# fab-psoc.net
KiCad netlist of a schematic drawn in EAGLE
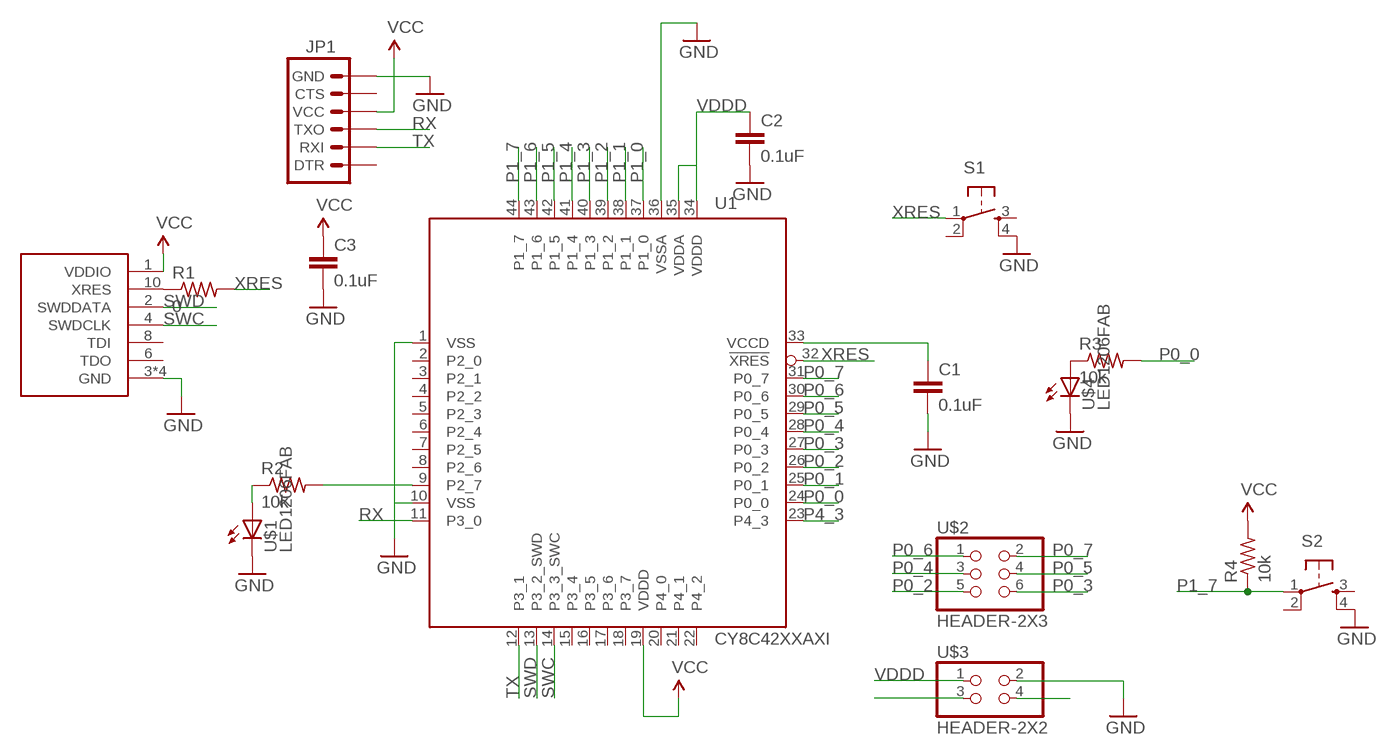
[diagram p0: schematic, sheet 1]

(export (version "E")
  (design (tool "Eeschema 10.0.6"))
  (components
    (comp (ref "C1")
      (value "0.1uF")
      (footprint "eagle-import:C1206FAB")
      (libsource (lib "eagle-import") (part "CAPACITOR1206FAB"))
    )
    (comp (ref "C2")
      (value "0.1uF")
      (footprint "eagle-import:C1206FAB")
      (libsource (lib "eagle-import") (part "CAPACITOR1206FAB"))
    )
    (comp (ref "C3")
      (value "0.1uF")
      (footprint "eagle-import:C1206FAB")
      (libsource (lib "eagle-import") (part "CAPACITOR1206FAB"))
    )
    (comp (ref "JP1")
      (value "FTDI-SMD")
      (footprint "eagle-import:FTDI-SMD")
      (libsource (lib "eagle-import") (part "FTDI-SMD"))
    )
    (comp (ref "MINIPROG3")
      (value "MINIPROG")
      (footprint "eagle-import:2X5SMD")
      (libsource (lib "eagle-import") (part "MINIPROG"))
    )
    (comp (ref "R1")
      (value "0")
      (footprint "eagle-import:R1206FAB")
      (libsource (lib "eagle-import") (part "RESISTOR1206FAB"))
    )
    (comp (ref "R2")
      (value "10k")
      (footprint "eagle-import:R1206FAB")
      (libsource (lib "eagle-import") (part "RESISTOR1206FAB"))
    )
    (comp (ref "R3")
      (value "10k")
      (footprint "eagle-import:R1206FAB")
      (libsource (lib "eagle-import") (part "RESISTOR1206FAB"))
    )
    (comp (ref "R4")
      (value "10k")
      (footprint "eagle-import:R1206FAB")
      (libsource (lib "eagle-import") (part "RESISTOR1206FAB"))
    )
    (comp (ref "S1")
      (value "SWITCH")
      (footprint "eagle-import:SWITCH")
      (libsource (lib "eagle-import") (part "SWITCH"))
    )
    (comp (ref "S2")
      (value "SWITCH")
      (footprint "eagle-import:SWITCH")
      (libsource (lib "eagle-import") (part "SWITCH"))
    )
    (comp (ref "U$1")
      (value "LED1206FAB")
      (footprint "eagle-import:R1206FAB")
      (libsource (lib "eagle-import") (part "LED1206FAB"))
    )
    (comp (ref "U$2")
      (value "HEADER-2X3")
      (footprint "eagle-import:2X3SMD")
      (libsource (lib "eagle-import") (part "HEADER-2X3"))
    )
    (comp (ref "U$3")
      (value "HEADER-2X2")
      (footprint "eagle-import:2X2SMD")
      (libsource (lib "eagle-import") (part "HEADER-2X2"))
    )
    (comp (ref "U$4")
      (value "LED1206FAB")
      (footprint "eagle-import:R1206FAB")
      (libsource (lib "eagle-import") (part "LED1206FAB"))
    )
    (comp (ref "U1")
      (value "CY8C42XXAXI")
      (footprint "eagle-import:TQFP-10X10-44")
      (libsource (lib "eagle-import") (part "CY8C42XXAXI"))
    )
  )
  (nets
    (net (code "1") (name "/P0_0") (class "Default")
      (node (ref "R3") (pin "2") (pinfunction "2_2") (pintype "passive"))
      (node (ref "U1") (pin "24") (pinfunction "P0_0_24") (pintype "bidirectional"))
    )
    (net (code "2") (name "/P0_1") (class "Default")
      (node (ref "U1") (pin "25") (pinfunction "P0_1_25") (pintype "bidirectional"))
    )
    (net (code "3") (name "/P0_2") (class "Default")
      (node (ref "U$2") (pin "5") (pinfunction "5_5") (pintype "passive"))
      (node (ref "U1") (pin "26") (pinfunction "P0_2_26") (pintype "input"))
    )
    (net (code "4") (name "/P0_3") (class "Default")
      (node (ref "U$2") (pin "6") (pinfunction "6_6") (pintype "passive"))
      (node (ref "U1") (pin "27") (pinfunction "P0_3_27") (pintype "bidirectional"))
    )
    (net (code "5") (name "/P0_4") (class "Default")
      (node (ref "U$2") (pin "3") (pinfunction "3_3") (pintype "passive"))
      (node (ref "U1") (pin "28") (pinfunction "P0_4_28") (pintype "bidirectional"))
    )
    (net (code "6") (name "/P0_5") (class "Default")
      (node (ref "U$2") (pin "4") (pinfunction "4_4") (pintype "passive"))
      (node (ref "U1") (pin "29") (pinfunction "P0_5_29") (pintype "bidirectional"))
    )
    (net (code "7") (name "/P0_6") (class "Default")
      (node (ref "U$2") (pin "1") (pinfunction "1_1") (pintype "passive"))
      (node (ref "U1") (pin "30") (pinfunction "P0_6_30") (pintype "power_in"))
    )
    (net (code "8") (name "/P0_7") (class "Default")
      (node (ref "U$2") (pin "2") (pinfunction "2_2") (pintype "passive"))
      (node (ref "U1") (pin "31") (pinfunction "P0_7_31") (pintype "bidirectional"))
    )
    (net (code "9") (name "/P1_0") (class "Default")
      (node (ref "U1") (pin "37") (pinfunction "P1_0_37") (pintype "bidirectional"))
    )
    (net (code "10") (name "/P1_1") (class "Default")
      (node (ref "U1") (pin "38") (pinfunction "P1_1_38") (pintype "bidirectional"))
    )
    (net (code "11") (name "/P1_2") (class "Default")
      (node (ref "U1") (pin "39") (pinfunction "P1_2_39") (pintype "power_in"))
    )
    (net (code "12") (name "/P1_3") (class "Default")
      (node (ref "U1") (pin "40") (pinfunction "P1_3_40") (pintype "bidirectional"))
    )
    (net (code "13") (name "/P1_4") (class "Default")
      (node (ref "U1") (pin "41") (pinfunction "P1_4_41") (pintype "bidirectional"))
    )
    (net (code "14") (name "/P1_5") (class "Default")
      (node (ref "U1") (pin "42") (pinfunction "P1_5_42") (pintype "bidirectional"))
    )
    (net (code "15") (name "/P1_6") (class "Default")
      (node (ref "U1") (pin "43") (pinfunction "P1_6_43") (pintype "bidirectional"))
    )
    (net (code "16") (name "/P1_7") (class "Default")
      (node (ref "R4") (pin "1") (pinfunction "1_1") (pintype "passive"))
      (node (ref "S2") (pin "1") (pinfunction "P_1") (pintype "passive"))
      (node (ref "U1") (pin "44") (pinfunction "P1_7_44") (pintype "bidirectional"))
    )
    (net (code "17") (name "/P2_2") (class "Default")
      (node (ref "U1") (pin "4") (pinfunction "P2_2_4") (pintype "power_in"))
    )
    (net (code "18") (name "/P2_6") (class "Default")
      (node (ref "U1") (pin "8") (pinfunction "P2_6_8") (pintype "power_in"))
    )
    (net (code "19") (name "/P3_6") (class "Default")
      (node (ref "U1") (pin "17") (pinfunction "P3_6_17") (pintype "power_in"))
    )
    (net (code "20") (name "/P4_3") (class "Default")
      (node (ref "U1") (pin "23") (pinfunction "P4_3_23") (pintype "bidirectional"))
    )
    (net (code "21") (name "/RX") (class "Default")
      (node (ref "JP1") (pin "3") (pinfunction "TXO_3") (pintype "passive"))
      (node (ref "U1") (pin "11") (pinfunction "P3_0_11") (pintype "bidirectional"))
    )
    (net (code "22") (name "/SWC") (class "Default")
      (node (ref "MINIPROG3") (pin "4") (pinfunction "SWDCLK_4") (pintype "bidirectional"))
      (node (ref "U1") (pin "14") (pinfunction "P3_3_SWC_14") (pintype "bidirectional"))
    )
    (net (code "23") (name "/SWD") (class "Default")
      (node (ref "MINIPROG3") (pin "2") (pinfunction "SWDDATA_2") (pintype "bidirectional"))
      (node (ref "U1") (pin "13") (pinfunction "P3_2_SWD_13") (pintype "bidirectional"))
    )
    (net (code "24") (name "/TX") (class "Default")
      (node (ref "JP1") (pin "2") (pinfunction "RXI_2") (pintype "passive"))
      (node (ref "U1") (pin "12") (pinfunction "P3_1_12") (pintype "bidirectional"))
    )
    (net (code "25") (name "/VDDD") (class "Default")
      (node (ref "C2") (pin "1") (pinfunction "1_1") (pintype "passive"))
      (node (ref "U$3") (pin "1") (pinfunction "1_1") (pintype "passive"))
      (node (ref "U1") (pin "34") (pinfunction "VDDD_34") (pintype "bidirectional"))
      (node (ref "U1") (pin "35") (pinfunction "VDDA_35") (pintype "bidirectional"))
    )
    (net (code "26") (name "/XRES") (class "Default")
      (node (ref "R1") (pin "2") (pinfunction "2_2") (pintype "passive"))
      (node (ref "S1") (pin "1") (pinfunction "P_1") (pintype "passive"))
      (node (ref "U1") (pin "32") (pinfunction "~{XRES}_32") (pintype "bidirectional"))
    )
    (net (code "27") (name "GND") (class "Default")
      (node (ref "C1") (pin "2") (pinfunction "2_2") (pintype "passive"))
      (node (ref "C2") (pin "2") (pinfunction "2_2") (pintype "passive"))
      (node (ref "C3") (pin "2") (pinfunction "2_2") (pintype "passive"))
      (node (ref "JP1") (pin "6") (pinfunction "GND_6") (pintype "passive"))
      (node (ref "MINIPROG3") (pin "3") (pinfunction "GND_3") (pintype "bidirectional"))
      (node (ref "MINIPROG3") (pin "5") (pinfunction "GND_5") (pintype "bidirectional"))
      (node (ref "MINIPROG3") (pin "7") (pinfunction "GND_7") (pintype "bidirectional"))
      (node (ref "MINIPROG3") (pin "9") (pinfunction "GND_9") (pintype "bidirectional"))
      (node (ref "S1") (pin "4") (pinfunction "S1_4") (pintype "passive"))
      (node (ref "S2") (pin "4") (pinfunction "S1_4") (pintype "passive"))
      (node (ref "U$1") (pin "2") (pinfunction "C_2") (pintype "passive"))
      (node (ref "U$3") (pin "2") (pinfunction "2_2") (pintype "passive"))
      (node (ref "U$4") (pin "2") (pinfunction "C_2") (pintype "passive"))
      (node (ref "U1") (pin "1") (pinfunction "VSS_1") (pintype "bidirectional"))
      (node (ref "U1") (pin "10") (pinfunction "VSS_10") (pintype "bidirectional"))
      (node (ref "U1") (pin "36") (pinfunction "VSSA_36") (pintype "bidirectional"))
    )
    (net (code "28") (name "Net-(MINIPROG3-XRES)") (class "Default")
      (node (ref "MINIPROG3") (pin "10") (pinfunction "XRES_10") (pintype "bidirectional"))
      (node (ref "R1") (pin "1") (pinfunction "1_1") (pintype "passive"))
    )
    (net (code "29") (name "Net-(U$1-A)") (class "Default")
      (node (ref "R2") (pin "1") (pinfunction "1_1") (pintype "passive"))
      (node (ref "U$1") (pin "1") (pinfunction "A_1") (pintype "passive"))
    )
    (net (code "30") (name "Net-(U$4-A)") (class "Default")
      (node (ref "R3") (pin "1") (pinfunction "1_1") (pintype "passive"))
      (node (ref "U$4") (pin "1") (pinfunction "A_1") (pintype "passive"))
    )
    (net (code "31") (name "Net-(U1-P2_7)") (class "Default")
      (node (ref "R2") (pin "2") (pinfunction "2_2") (pintype "passive"))
      (node (ref "U1") (pin "9") (pinfunction "P2_7_9") (pintype "bidirectional"))
    )
    (net (code "32") (name "Net-(U1-VCCD)") (class "Default")
      (node (ref "C1") (pin "1") (pinfunction "1_1") (pintype "passive"))
      (node (ref "U1") (pin "33") (pinfunction "VCCD_33") (pintype "bidirectional"))
    )
    (net (code "33") (name "VCC") (class "Default")
      (node (ref "C3") (pin "1") (pinfunction "1_1") (pintype "passive"))
      (node (ref "JP1") (pin "4") (pinfunction "VCC_4") (pintype "passive"))
      (node (ref "MINIPROG3") (pin "1") (pinfunction "VDDIO_1") (pintype "bidirectional"))
      (node (ref "R4") (pin "2") (pinfunction "2_2") (pintype "passive"))
      (node (ref "U1") (pin "19") (pinfunction "VDDD_19") (pintype "bidirectional"))
    )
    (net (code "34") (name "unconnected-(JP1-CTS-Pad5)") (class "Default")
      (node (ref "JP1") (pin "5") (pinfunction "CTS_5") (pintype "passive"))
    )
    (net (code "35") (name "unconnected-(JP1-DTR-Pad1)") (class "Default")
      (node (ref "JP1") (pin "1") (pinfunction "DTR_1") (pintype "passive"))
    )
    (net (code "36") (name "unconnected-(MINIPROG3-TDI-Pad8)") (class "Default")
      (node (ref "MINIPROG3") (pin "8") (pinfunction "TDI_8") (pintype "bidirectional"))
    )
    (net (code "37") (name "unconnected-(MINIPROG3-TDO-Pad6)") (class "Default")
      (node (ref "MINIPROG3") (pin "6") (pinfunction "TDO_6") (pintype "bidirectional"))
    )
    (net (code "38") (name "unconnected-(S1-P1-Pad2)") (class "Default")
      (node (ref "S1") (pin "2") (pinfunction "P1_2") (pintype "passive"))
    )
    (net (code "39") (name "unconnected-(S1-S-Pad3)") (class "Default")
      (node (ref "S1") (pin "3") (pinfunction "S_3") (pintype "passive"))
    )
    (net (code "40") (name "unconnected-(S2-P1-Pad2)") (class "Default")
      (node (ref "S2") (pin "2") (pinfunction "P1_2") (pintype "passive"))
    )
    (net (code "41") (name "unconnected-(S2-S-Pad3)") (class "Default")
      (node (ref "S2") (pin "3") (pinfunction "S_3") (pintype "passive"))
    )
    (net (code "42") (name "unconnected-(U$3-Pad3)") (class "Default")
      (node (ref "U$3") (pin "3") (pinfunction "3_3") (pintype "passive"))
    )
    (net (code "43") (name "unconnected-(U$3-Pad4)") (class "Default")
      (node (ref "U$3") (pin "4") (pinfunction "4_4") (pintype "passive"))
    )
    (net (code "44") (name "unconnected-(U1-P2_0-Pad2)") (class "Default")
      (node (ref "U1") (pin "2") (pinfunction "P2_0_2") (pintype "bidirectional"))
    )
    (net (code "45") (name "unconnected-(U1-P2_1-Pad3)") (class "Default")
      (node (ref "U1") (pin "3") (pinfunction "P2_1_3") (pintype "bidirectional"))
    )
    (net (code "46") (name "unconnected-(U1-P2_3-Pad5)") (class "Default")
      (node (ref "U1") (pin "5") (pinfunction "P2_3_5") (pintype "bidirectional"))
    )
    (net (code "47") (name "unconnected-(U1-P2_4-Pad6)") (class "Default")
      (node (ref "U1") (pin "6") (pinfunction "P2_4_6") (pintype "bidirectional"))
    )
    (net (code "48") (name "unconnected-(U1-P2_5-Pad7)") (class "Default")
      (node (ref "U1") (pin "7") (pinfunction "P2_5_7") (pintype "bidirectional"))
    )
    (net (code "49") (name "unconnected-(U1-P3_4-Pad15)") (class "Default")
      (node (ref "U1") (pin "15") (pinfunction "P3_4_15") (pintype "bidirectional"))
    )
    (net (code "50") (name "unconnected-(U1-P3_5-Pad16)") (class "Default")
      (node (ref "U1") (pin "16") (pinfunction "P3_5_16") (pintype "bidirectional"))
    )
    (net (code "51") (name "unconnected-(U1-P3_7-Pad18)") (class "Default")
      (node (ref "U1") (pin "18") (pinfunction "P3_7_18") (pintype "bidirectional"))
    )
    (net (code "52") (name "unconnected-(U1-P4_0-Pad20)") (class "Default")
      (node (ref "U1") (pin "20") (pinfunction "P4_0_20") (pintype "bidirectional"))
    )
    (net (code "53") (name "unconnected-(U1-P4_1-Pad21)") (class "Default")
      (node (ref "U1") (pin "21") (pinfunction "P4_1_21") (pintype "bidirectional"))
    )
    (net (code "54") (name "unconnected-(U1-P4_2-Pad22)") (class "Default")
      (node (ref "U1") (pin "22") (pinfunction "P4_2_22") (pintype "bidirectional"))
    )
  )
)
